# pwm_nmos_555.net
KiCad netlist of a schematic drawn in EAGLE
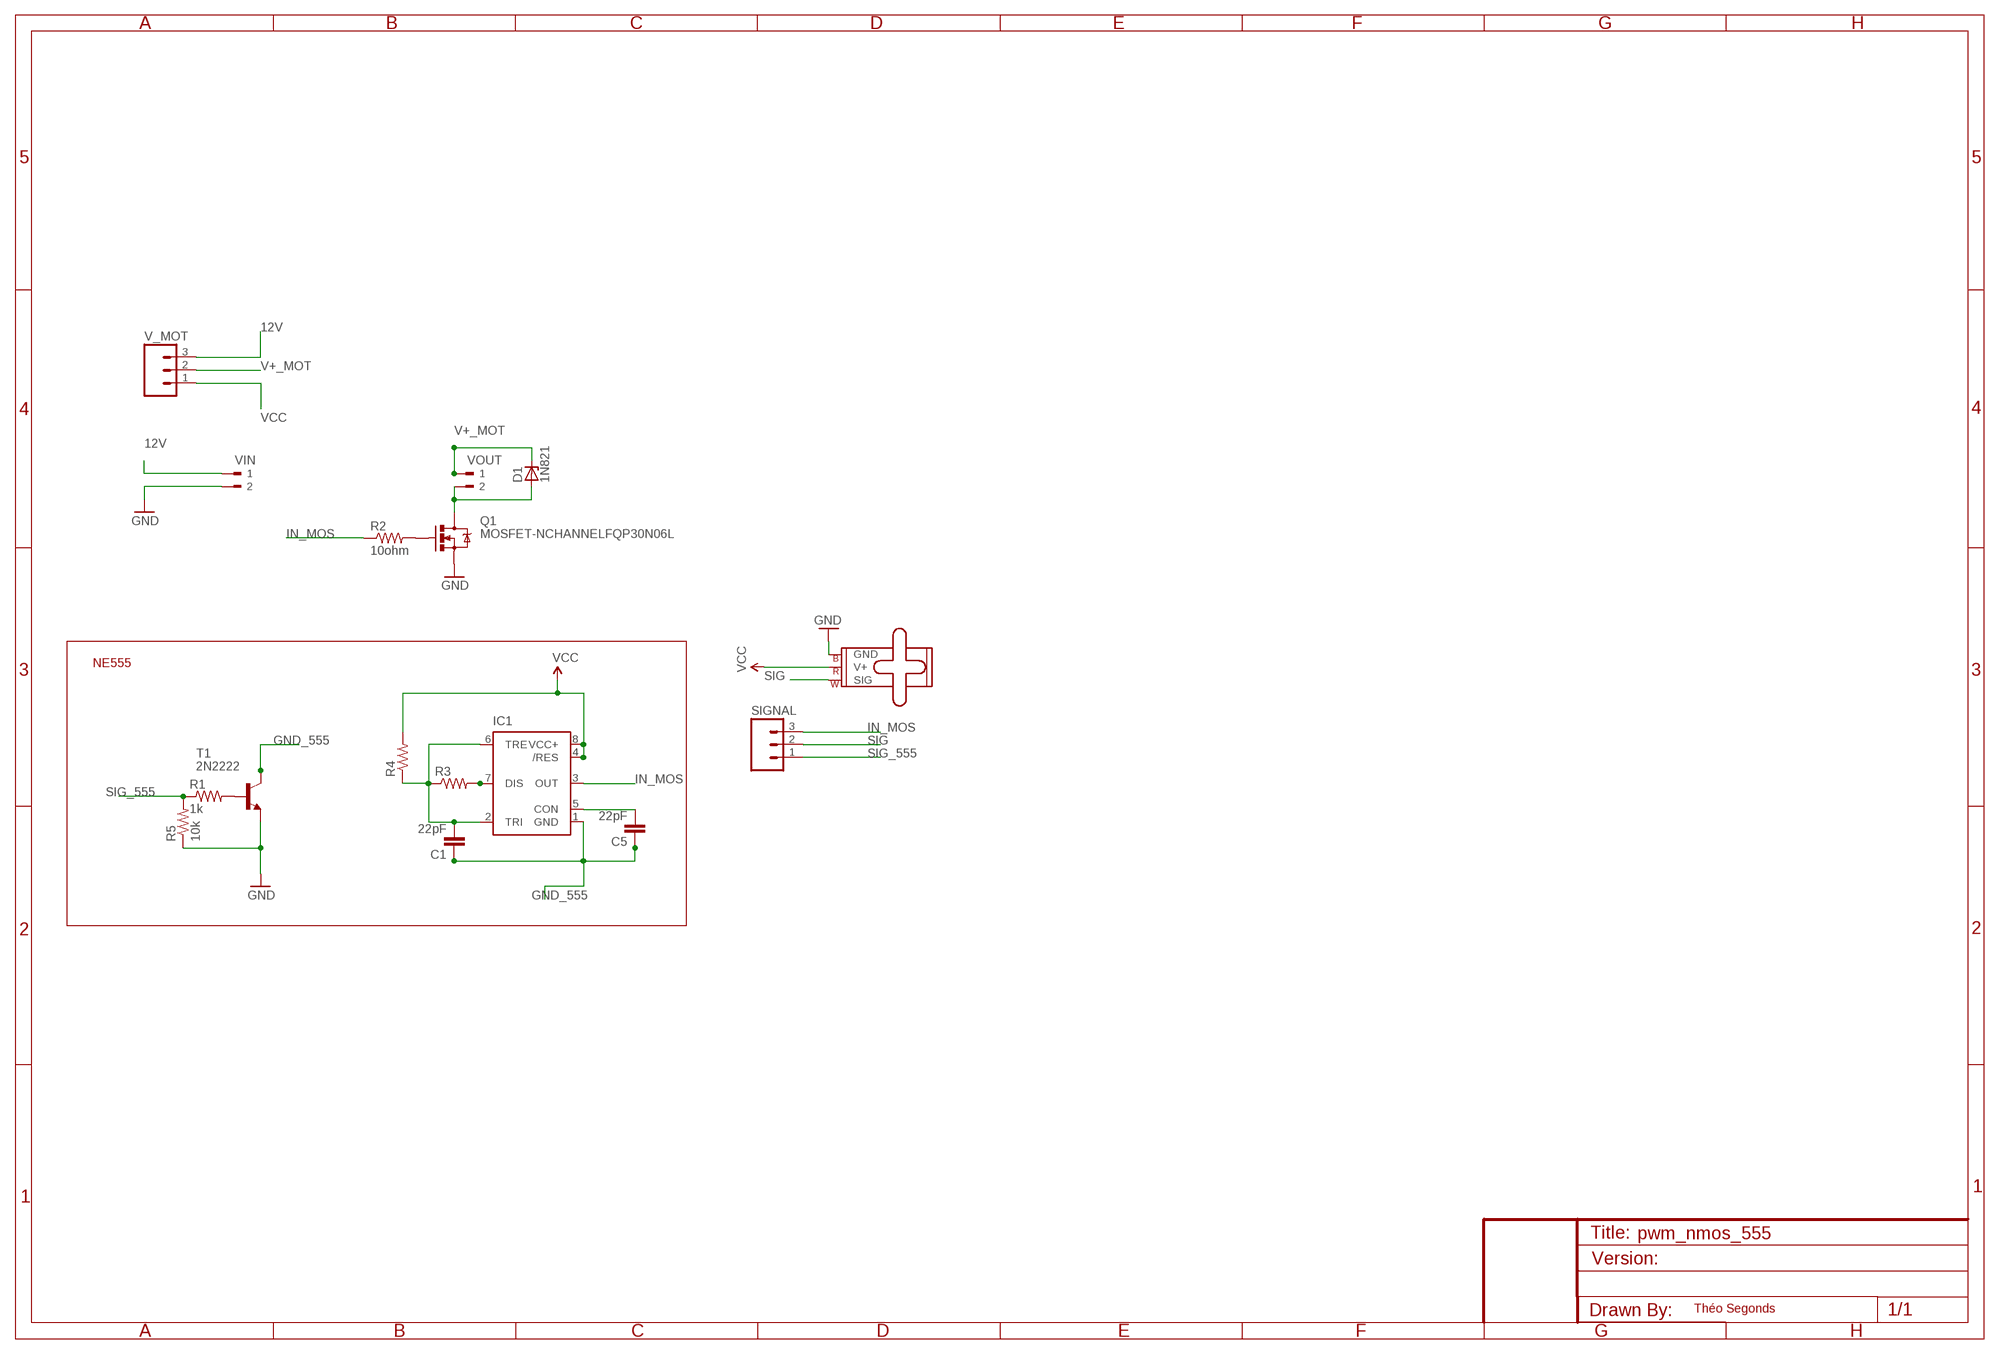
[diagram p0: schematic, sheet 1]

(export (version "E")
  (design (tool "Eeschema 10.0.6"))
  (components
    (comp (ref "C1")
      (value "22pF")
      (footprint "eagle-import:0805")
      (fields (field (name "MF") "AVX") (field (name "MPN") "08055A220JAT2A"))
      (libsource (lib "eagle-import") (part "CAP0805"))
    )
    (comp (ref "C5")
      (value "22pF")
      (footprint "eagle-import:0805")
      (fields (field (name "MF") "AVX") (field (name "MPN") "08055A220JAT2A"))
      (libsource (lib "eagle-import") (part "CAP0805"))
    )
    (comp (ref "D1")
      (value "1N821")
      (footprint "eagle-import:DO35Z10")
      (libsource (lib "eagle-import") (part "1N821"))
    )
    (comp (ref "IC1")
      (value "NE555P")
      (footprint "eagle-import:DIL-08")
      (fields (field (name "MF") "Arrow Electronics") (field (name "MPN") "NE555N"))
      (libsource (lib "eagle-import") (part "NE555P"))
    )
    (comp (ref "INPUT")
      (value "SMALL_SERVO")
      (footprint "eagle-import:1X03")
      (libsource (lib "eagle-import") (part "SMALL_SERVO"))
    )
    (comp (ref "Q1")
      (value "MOSFET-NCHANNELFQP30N06L")
      (footprint "eagle-import:TO220V")
      (libsource (lib "eagle-import") (part "MOSFET-NCHANNELFQP30N06L"))
    )
    (comp (ref "R1")
      (value "1k")
      (footprint "eagle-import:0805")
      (libsource (lib "eagle-import") (part "RESISTOR0805-RES"))
    )
    (comp (ref "R2")
      (value "10ohm")
      (footprint "eagle-import:0805")
      (libsource (lib "eagle-import") (part "RESISTOR0805-RES"))
    )
    (comp (ref "R3")
      (value "RESISTOR0805-RES")
      (footprint "eagle-import:0805")
      (libsource (lib "eagle-import") (part "RESISTOR0805-RES"))
    )
    (comp (ref "R4")
      (value "RESISTOR0805-RES")
      (footprint "eagle-import:0805")
      (libsource (lib "eagle-import") (part "RESISTOR0805-RES"))
    )
    (comp (ref "R5")
      (value "10k")
      (footprint "eagle-import:0805")
      (libsource (lib "eagle-import") (part "RESISTOR0805-RES"))
    )
    (comp (ref "SIGNAL")
      (value "M03PTH")
      (footprint "eagle-import:1X03")
      (libsource (lib "eagle-import") (part "M03PTH"))
    )
    (comp (ref "T1")
      (value "2N2222")
      (footprint "eagle-import:TO92-EBC-OVAL")
      (libsource (lib "eagle-import") (part "2N2222"))
    )
    (comp (ref "VIN")
      (value "90-2")
      (footprint "eagle-import:90-2")
      (libsource (lib "eagle-import") (part "90-2"))
    )
    (comp (ref "VOUT")
      (value "90-2")
      (footprint "eagle-import:90-2")
      (libsource (lib "eagle-import") (part "90-2"))
    )
    (comp (ref "V_MOT")
      (value "M03PTH")
      (footprint "eagle-import:1X03")
      (libsource (lib "eagle-import") (part "M03PTH"))
    )
  )
  (nets
    (net (code "1") (name "/12V") (class "Default")
      (node (ref "VIN") (pin "1") (pinfunction "1_1") (pintype "passive"))
      (node (ref "V_MOT") (pin "3") (pinfunction "3_3") (pintype "passive"))
    )
    (net (code "2") (name "/GND_555") (class "Default")
      (node (ref "C1") (pin "1") (pinfunction "1_1") (pintype "passive"))
      (node (ref "C5") (pin "1") (pinfunction "1_1") (pintype "passive"))
      (node (ref "IC1") (pin "1") (pinfunction "GND_1") (pintype "power_in"))
      (node (ref "T1") (pin "C") (pinfunction "C_C") (pintype "passive"))
    )
    (net (code "3") (name "/IN_MOS") (class "Default")
      (node (ref "IC1") (pin "3") (pinfunction "OUT_3") (pintype "output"))
      (node (ref "R2") (pin "1") (pinfunction "1_1") (pintype "passive"))
      (node (ref "SIGNAL") (pin "3") (pinfunction "3_3") (pintype "passive"))
    )
    (net (code "4") (name "/SIG") (class "Default")
      (node (ref "INPUT") (pin "1") (pinfunction "SIG_1") (pintype "bidirectional"))
      (node (ref "SIGNAL") (pin "2") (pinfunction "2_2") (pintype "passive"))
    )
    (net (code "5") (name "/SIG_555") (class "Default")
      (node (ref "R1") (pin "1") (pinfunction "1_1") (pintype "passive"))
      (node (ref "R5") (pin "2") (pinfunction "2_2") (pintype "passive"))
      (node (ref "SIGNAL") (pin "1") (pinfunction "1_1") (pintype "passive"))
    )
    (net (code "6") (name "/V+_MOT") (class "Default")
      (node (ref "D1") (pin "C") (pinfunction "C_C") (pintype "passive"))
      (node (ref "VOUT") (pin "1") (pinfunction "1_1") (pintype "passive"))
      (node (ref "V_MOT") (pin "2") (pinfunction "2_2") (pintype "passive"))
    )
    (net (code "7") (name "GND") (class "Default")
      (node (ref "INPUT") (pin "3") (pinfunction "GND_3") (pintype "bidirectional"))
      (node (ref "Q1") (pin "3") (pinfunction "S_3") (pintype "passive"))
      (node (ref "R5") (pin "1") (pinfunction "1_1") (pintype "passive"))
      (node (ref "T1") (pin "E") (pinfunction "E_E") (pintype "passive"))
      (node (ref "VIN") (pin "2") (pinfunction "2_2") (pintype "passive"))
    )
    (net (code "8") (name "Net-(IC1-CON)") (class "Default")
      (node (ref "C5") (pin "2") (pinfunction "2_2") (pintype "passive"))
      (node (ref "IC1") (pin "5") (pinfunction "CON_5") (pintype "input"))
    )
    (net (code "9") (name "Net-(IC1-DIS)") (class "Default")
      (node (ref "IC1") (pin "7") (pinfunction "DIS_7") (pintype "input"))
      (node (ref "R3") (pin "2") (pinfunction "2_2") (pintype "passive"))
    )
    (net (code "10") (name "Net-(IC1-TRE)") (class "Default")
      (node (ref "C1") (pin "2") (pinfunction "2_2") (pintype "passive"))
      (node (ref "IC1") (pin "2") (pinfunction "TRI_2") (pintype "input"))
      (node (ref "IC1") (pin "6") (pinfunction "TRE_6") (pintype "input"))
      (node (ref "R3") (pin "1") (pinfunction "1_1") (pintype "passive"))
      (node (ref "R4") (pin "1") (pinfunction "1_1") (pintype "passive"))
    )
    (net (code "11") (name "Net-(Q1-D)") (class "Default")
      (node (ref "D1") (pin "A") (pinfunction "A_A") (pintype "passive"))
      (node (ref "Q1") (pin "2") (pinfunction "D_2") (pintype "passive"))
      (node (ref "VOUT") (pin "2") (pinfunction "2_2") (pintype "passive"))
    )
    (net (code "12") (name "Net-(Q1-G)") (class "Default")
      (node (ref "Q1") (pin "1") (pinfunction "G_1") (pintype "passive"))
      (node (ref "R2") (pin "2") (pinfunction "2_2") (pintype "passive"))
    )
    (net (code "13") (name "Net-(R1-Pad2)") (class "Default")
      (node (ref "R1") (pin "2") (pinfunction "2_2") (pintype "passive"))
      (node (ref "T1") (pin "B") (pinfunction "B_B") (pintype "passive"))
    )
    (net (code "14") (name "VCC") (class "Default")
      (node (ref "IC1") (pin "4") (pinfunction "/RES_4") (pintype "input"))
      (node (ref "IC1") (pin "8") (pinfunction "VCC+_8") (pintype "power_in"))
      (node (ref "INPUT") (pin "2") (pinfunction "V+_2") (pintype "bidirectional"))
      (node (ref "R4") (pin "2") (pinfunction "2_2") (pintype "passive"))
      (node (ref "V_MOT") (pin "1") (pinfunction "1_1") (pintype "passive"))
    )
  )
)
